# Buck_Converter.net
KiCad netlist of a schematic drawn in Altium Designer
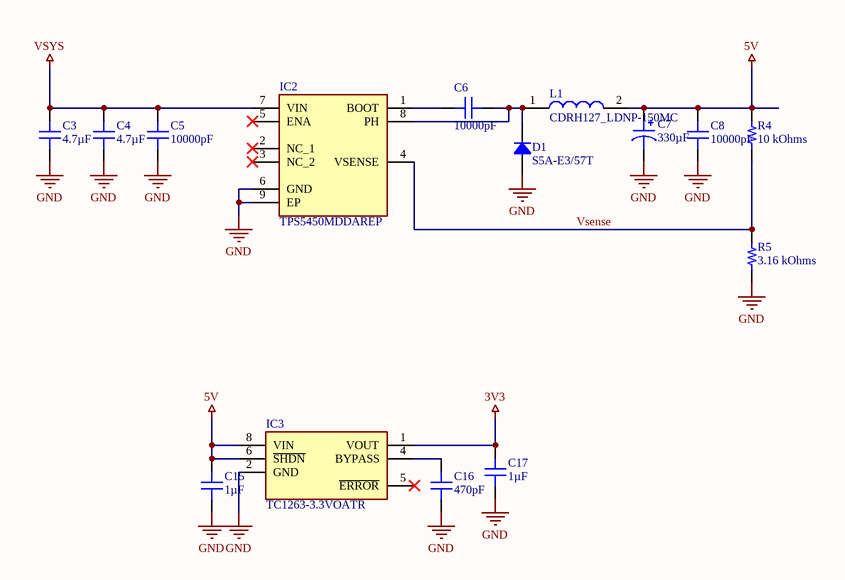
[diagram p0: Buck Converter.SchDoc]

(export (version "E")
  (design (tool "Eeschema 10.0.6"))
  (components
    (comp (ref "C3")
      (value "4.7µF")
      (footprint "CAP 1206_3216 - 1.0MM")
      (description "CAP CER 4.7UF 25V X7R 1206")
      (fields
        (field (name "PART NUMBER") "C3216X7R1E475K085AB")
        (field (name "MANUFACTURER") "TDK Corporation")
      )
      (libsource (lib "Celestial Altium Library - altium_library") (part "Capacitor"))
    )
    (comp (ref "C4")
      (value "4.7µF")
      (footprint "CAP 1206_3216 - 1.0MM")
      (description "CAP CER 4.7UF 25V X7R 1206")
      (fields
        (field (name "PART NUMBER") "C3216X7R1E475K085AB")
        (field (name "MANUFACTURER") "TDK Corporation")
      )
      (libsource (lib "Celestial Altium Library - altium_library") (part "Capacitor"))
    )
    (comp (ref "C5")
      (value "10000pF")
      (footprint "CAP 0603_1608")
      (description "CE SMD 0603 .01UF 10% 50V X7R 2M")
      (fields (field (name "PART NUMBER") "C0603C103K5RAC7081") (field (name "MANUFACTURER") "KEMET"))
      (libsource (lib "Celestial Altium Library - altium_library") (part "Capacitor"))
    )
    (comp (ref "C6")
      (value "10000pF")
      (footprint "CAP 0603_1608")
      (description "CE SMD 0603 .01UF 10% 50V X7R 2M")
      (fields (field (name "PART NUMBER") "C0603C103K5RAC7081") (field (name "MANUFACTURER") "KEMET"))
      (libsource (lib "Celestial Altium Library - altium_library") (part "Capacitor"))
    )
    (comp (ref "C7")
      (value "330µF")
      (footprint "CAP ALSMD 6.6MM H7.7MM")
      (description "CAP ALUM POLY 330UF 20% 10V SMD")
      (fields (field (name "PART NUMBER") "875105245015") (field (name "MANUFACTURER") "Würth Elektronik"))
      (libsource (lib "Celestial Altium Library - altium_library") (part "Polarised Capacitor"))
    )
    (comp (ref "C8")
      (value "10000pF")
      (footprint "CAP 0603_1608")
      (description "CE SMD 0603 .01UF 10% 50V X7R 2M")
      (fields (field (name "PART NUMBER") "C0603C103K5RAC7081") (field (name "MANUFACTURER") "KEMET"))
      (libsource (lib "Celestial Altium Library - altium_library") (part "Capacitor"))
    )
    (comp (ref "C15")
      (value "1µF")
      (footprint "CAP 0603_1608")
      (description "CAP CER 0603 1UF 16V X7R 10%")
      (fields (field (name "PART NUMBER") "C0603C105K4RACAUTO") (field (name "MANUFACTURER") "KEMET"))
      (libsource (lib "Celestial Altium Library - altium_library") (part "Capacitor"))
    )
    (comp (ref "C16")
      (value "470pF")
      (footprint "CAP 0603_1608")
      (description "CAP CER 470PF 25V C0G/NP0 0603")
      (fields (field (name "PART NUMBER") "C0603C471J3GACAUTO") (field (name "MANUFACTURER") "KEMET"))
      (libsource (lib "Celestial Altium Library - altium_library") (part "Capacitor"))
    )
    (comp (ref "C17")
      (value "1µF")
      (footprint "CAP 0603_1608")
      (description "CAP CER 0603 1UF 16V X7R 10%")
      (fields (field (name "PART NUMBER") "C0603C105K4RACAUTO") (field (name "MANUFACTURER") "KEMET"))
      (libsource (lib "Celestial Altium Library - altium_library") (part "Capacitor"))
    )
    (comp (ref "D1")
      (value "S5A-E3/57T")
      (footprint "DO214AB SMC")
      (description "DIODE GEN PURP 50V 5A DO214AB")
      (fields (field (name "MANUFACTURER") "Vishay Semiconductor Diodes Division"))
      (libsource (lib "Celestial Altium Library - altium_library") (part "Diode"))
    )
    (comp (ref "IC2")
      (value "TPS5450MDDAREP")
      (footprint "SamacSys:SOIC127P600X170-9N")
      (description "Integrated Circuit")
      (libsource (lib "SamacSys") (part "TPS5450MDDAREP"))
    )
    (comp (ref "IC3")
      (value "TC1263-3.3VOATR")
      (footprint "SamacSys:SOIC127P600X175-8N")
      (description "Integrated Circuit")
      (fields (field (name "MOUSER PART NUMBER") "579-TC1263-3.3VOATR"))
      (libsource (lib "SamacSys") (part "TC1263-3.3VOATR"))
    )
    (comp (ref "L1")
      (value "CDRH127_LDNP-150MC")
      (footprint "SamacSys:INDPM120120X800N")
      (description "Inductor")
      (fields
        (field (name "MANUFACTURER_PART_NUMBER") "CDRH127/LDNP-150MC")
        (field (name "MOUSER PART NUMBER") "851-CDRH127LDNP150MC")
      )
      (libsource (lib "*") (part "CDRH127_LDNP-150MC"))
    )
    (comp (ref "R4")
      (value "10 kOhms")
      (footprint "RES 0603_1608")
      (description "RES SMD 10K OHM 1% 1/10W 0603")
      (fields (field (name "PART NUMBER") "AF0603FR-0710KL") (field (name "MANUFACTURER") "Yageo"))
      (libsource (lib "Celestial Altium Library - altium_library") (part "Resistor"))
    )
    (comp (ref "R5")
      (value "3.16 kOhms")
      (footprint "RES 0603_1608")
      (description "RES SMD 3.16K OHM 1% 1/10W 0603")
      (fields (field (name "PART NUMBER") "CR0603-FX-3161ELF") (field (name "MANUFACTURER") "Bourns Inc."))
      (libsource (lib "Celestial Altium Library - altium_library") (part "Resistor"))
    )
  )
  (nets
    (net (code "1") (name "/Vsense") (class "Default")
      (node (ref "IC2") (pin "4") (pinfunction "VSENSE_4") (pintype "passive"))
      (node (ref "R4") (pin "1") (pinfunction "1_1") (pintype "passive"))
      (node (ref "R5") (pin "2") (pinfunction "2_2") (pintype "passive"))
    )
    (net (code "2") (name "3V3") (class "Default")
      (node (ref "C17") (pin "2") (pinfunction "2_2") (pintype "passive"))
      (node (ref "IC3") (pin "1") (pinfunction "VOUT_1") (pintype "passive"))
    )
    (net (code "3") (name "5V") (class "Default")
      (node (ref "C15") (pin "2") (pinfunction "2_2") (pintype "passive"))
      (node (ref "C7") (pin "1") (pinfunction "1_1") (pintype "passive"))
      (node (ref "C8") (pin "2") (pinfunction "2_2") (pintype "passive"))
      (node (ref "IC3") (pin "6") (pinfunction "~{SHDN}_6") (pintype "passive"))
      (node (ref "IC3") (pin "8") (pinfunction "VIN_8") (pintype "passive"))
      (node (ref "L1") (pin "2") (pinfunction "2_2") (pintype "passive"))
      (node (ref "R4") (pin "2") (pinfunction "2_2") (pintype "passive"))
    )
    (net (code "4") (name "GND") (class "Default")
      (node (ref "C15") (pin "1") (pinfunction "1_1") (pintype "passive"))
      (node (ref "C16") (pin "1") (pinfunction "1_1") (pintype "passive"))
      (node (ref "C17") (pin "1") (pinfunction "1_1") (pintype "passive"))
      (node (ref "C3") (pin "1") (pinfunction "1_1") (pintype "passive"))
      (node (ref "C4") (pin "1") (pinfunction "1_1") (pintype "passive"))
      (node (ref "C5") (pin "1") (pinfunction "1_1") (pintype "passive"))
      (node (ref "C7") (pin "2") (pinfunction "2_2") (pintype "passive"))
      (node (ref "C8") (pin "1") (pinfunction "1_1") (pintype "passive"))
      (node (ref "D1") (pin "1") (pinfunction "1_1") (pintype "passive"))
      (node (ref "IC2") (pin "6") (pinfunction "GND_6") (pintype "passive"))
      (node (ref "IC2") (pin "9") (pinfunction "EP_9") (pintype "passive"))
      (node (ref "IC3") (pin "2") (pinfunction "GND_2") (pintype "passive"))
      (node (ref "R5") (pin "1") (pinfunction "1_1") (pintype "passive"))
    )
    (net (code "5") (name "Net-(IC2-BOOT)") (class "Default")
      (node (ref "C6") (pin "2") (pinfunction "2_2") (pintype "passive"))
      (node (ref "IC2") (pin "1") (pinfunction "BOOT_1") (pintype "passive"))
    )
    (net (code "6") (name "Net-(IC2-PH)") (class "Default")
      (node (ref "C6") (pin "1") (pinfunction "1_1") (pintype "passive"))
      (node (ref "D1") (pin "2") (pinfunction "2_2") (pintype "passive"))
      (node (ref "IC2") (pin "8") (pinfunction "PH_8") (pintype "passive"))
      (node (ref "L1") (pin "1") (pinfunction "1_1") (pintype "passive"))
    )
    (net (code "7") (name "Net-(IC3-BYPASS)") (class "Default")
      (node (ref "C16") (pin "2") (pinfunction "2_2") (pintype "passive"))
      (node (ref "IC3") (pin "4") (pinfunction "BYPASS_4") (pintype "passive"))
    )
    (net (code "8") (name "VSYS") (class "Default")
      (node (ref "C3") (pin "2") (pinfunction "2_2") (pintype "passive"))
      (node (ref "C4") (pin "2") (pinfunction "2_2") (pintype "passive"))
      (node (ref "C5") (pin "2") (pinfunction "2_2") (pintype "passive"))
      (node (ref "IC2") (pin "7") (pinfunction "VIN_7") (pintype "passive"))
    )
    (net (code "9") (name "unconnected-(IC2-ENA-Pad5)") (class "Default")
      (node (ref "IC2") (pin "5") (pinfunction "ENA_5") (pintype "passive+no_connect"))
    )
    (net (code "10") (name "unconnected-(IC2-NC_1-Pad2)") (class "Default")
      (node (ref "IC2") (pin "2") (pinfunction "NC_1_2") (pintype "passive+no_connect"))
    )
    (net (code "11") (name "unconnected-(IC2-NC_2-Pad3)") (class "Default")
      (node (ref "IC2") (pin "3") (pinfunction "NC_2_3") (pintype "passive+no_connect"))
    )
    (net (code "12") (name "unconnected-(IC3-~{ERROR}-Pad5)") (class "Default")
      (node (ref "IC3") (pin "5") (pinfunction "~{ERROR}_5") (pintype "passive+no_connect"))
    )
  )
)
